# Darlington.net
KiCad netlist of a schematic drawn in Altium Designer
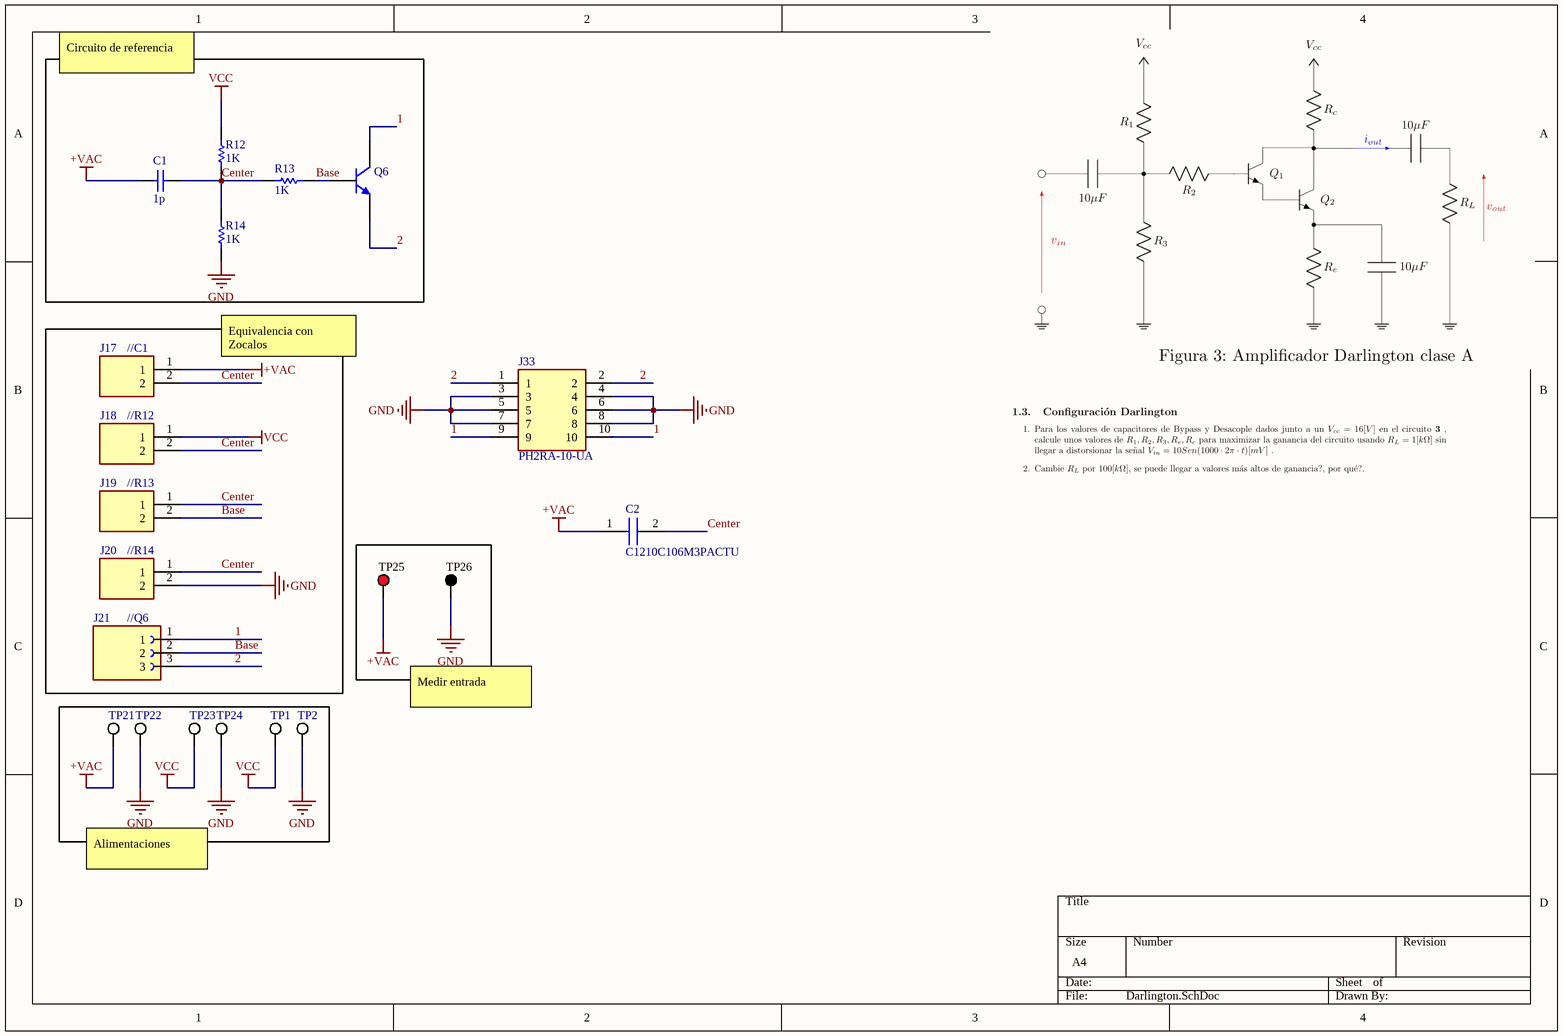
[diagram p0: Darlington.SchDoc]

(export (version "E")
  (design (tool "Eeschema 10.0.6"))
  (components
    (comp (ref "C1")
      (value "1p")
      (description "Capacitor")
      (libsource (lib "Simulation Generic Components") (part "Capacitor"))
    )
    (comp (ref "C2")
      (value "C1210C106M3PACTU")
      (footprint "Cap10uF:C1210")
      (description "Capacitor")
      (fields (field (name "MOUSER PART NUMBER") "80-C1210C106M3P"))
      (libsource (lib "Cap10uF") (part "C1210C106M3PACTU"))
    )
    (comp (ref "J17")
      (value "D01-9970242")
      (footprint "D019970242")
      (description "IC Socket: 2 Pos Receptacle SIL Straight THT Strip")
      (fields (field (name "MOUSER PART NUMBER") "855-D01-9970242"))
      (libsource (lib "Zocalo_2pines") (part "D01-9970242"))
    )
    (comp (ref "J18")
      (value "D01-9970242")
      (footprint "D019970242")
      (description "IC Socket: 2 Pos Receptacle SIL Straight THT Strip")
      (fields (field (name "MOUSER PART NUMBER") "855-D01-9970242"))
      (libsource (lib "Zocalo_2pines") (part "D01-9970242"))
    )
    (comp (ref "J19")
      (value "D01-9970242")
      (footprint "D019970242")
      (description "IC Socket: 2 Pos Receptacle SIL Straight THT Strip")
      (fields (field (name "MOUSER PART NUMBER") "855-D01-9970242"))
      (libsource (lib "Zocalo_2pines") (part "D01-9970242"))
    )
    (comp (ref "J20")
      (value "D01-9970242")
      (footprint "D019970242")
      (description "IC Socket: 2 Pos Receptacle SIL Straight THT Strip")
      (fields (field (name "MOUSER PART NUMBER") "855-D01-9970242"))
      (libsource (lib "Zocalo_2pines") (part "D01-9970242"))
    )
    (comp (ref "J21")
      (value "D01-9970342")
      (footprint "HARWIN_D01-9970342")
      (libsource (lib "Zocalo_3pines") (part "D01-9970342"))
    )
    (comp (ref "J33")
      (value "PH2RA-10-UA")
      (footprint "HDRRA10W64P254_2X5_1270X250X538P")
      (description "CONN HEADER R/A 10POS 2.54MM")
      (fields (field (name "MOUSER PART NUMBER") "737-PH2RA-10-UA"))
      (libsource (lib "PH2RA-10-UA") (part "PH2RA-10-UA"))
    )
    (comp (ref "Q6")
      (value "Bipolar NPN 3 Pins Transistor VBIC Model")
      (libsource (lib "Simulation Generic Components") (part "BJT NPN VBIC"))
    )
    (comp (ref "R12")
      (value "1K")
      (description "Resistor")
      (libsource (lib "Simulation Generic Components") (part "Resistor"))
    )
    (comp (ref "R13")
      (value "1K")
      (description "Resistor")
      (libsource (lib "Simulation Generic Components") (part "Resistor"))
    )
    (comp (ref "R14")
      (value "1K")
      (description "Resistor")
      (libsource (lib "Simulation Generic Components") (part "Resistor"))
    )
    (comp (ref "TP1")
      (value "575-4")
      (footprint "KSTN-575-4")
      (description "Banana Jack, Non-Insulated, 1-Pin THD, RoHS, Bulk")
      (fields (field (name "MANUFACTURER") "Keystone-Electronics"))
      (libsource (lib "Altium Content Vault") (part "TESTPOINT_WHITE"))
    )
    (comp (ref "TP2")
      (value "575-4")
      (footprint "KSTN-575-4")
      (description "Banana Jack, Non-Insulated, 1-Pin THD, RoHS, Bulk")
      (fields (field (name "MANUFACTURER") "Keystone-Electronics"))
      (libsource (lib "Altium Content Vault") (part "TESTPOINT_WHITE"))
    )
    (comp (ref "TP21")
      (value "575-4")
      (footprint "KSTN-575-4")
      (description "Banana Jack, Non-Insulated, 1-Pin THD, RoHS, Bulk")
      (fields (field (name "MANUFACTURER") "Keystone-Electronics"))
      (libsource (lib "Altium Content Vault") (part "TESTPOINT_WHITE"))
    )
    (comp (ref "TP22")
      (value "575-4")
      (footprint "KSTN-575-4")
      (description "Banana Jack, Non-Insulated, 1-Pin THD, RoHS, Bulk")
      (fields (field (name "MANUFACTURER") "Keystone-Electronics"))
      (libsource (lib "Altium Content Vault") (part "TESTPOINT_WHITE"))
    )
    (comp (ref "TP23")
      (value "575-4")
      (footprint "KSTN-575-4")
      (description "Banana Jack, Non-Insulated, 1-Pin THD, RoHS, Bulk")
      (fields (field (name "MANUFACTURER") "Keystone-Electronics"))
      (libsource (lib "Altium Content Vault") (part "TESTPOINT_WHITE"))
    )
    (comp (ref "TP24")
      (value "575-4")
      (footprint "KSTN-575-4")
      (description "Banana Jack, Non-Insulated, 1-Pin THD, RoHS, Bulk")
      (fields (field (name "MANUFACTURER") "Keystone-Electronics"))
      (libsource (lib "Altium Content Vault") (part "TESTPOINT_WHITE"))
    )
    (comp (ref "TP25")
      (value "5010")
      (footprint "KSTN-5010_V")
      (description "Test Point, Red, Through Hole, RoHS, Bulk")
      (fields (field (name "MANUFACTURER") "Keystone"))
      (libsource (lib "Altium Content Vault") (part "TESTPOINT_RED"))
    )
    (comp (ref "TP26")
      (value "5011")
      (footprint "KSTN-5011_V")
      (description "Test Point, Black, Through Hole, RoHS, Bulk")
      (fields (field (name "MANUFACTURER") "Keystone"))
      (libsource (lib "Altium Content Vault") (part "TESTPOINT_BLACK"))
    )
  )
  (nets
    (net (code "1") (name "+VAC") (class "Default")
      (node (ref "C1") (pin "1") (pinfunction "1_1") (pintype "passive"))
      (node (ref "C2") (pin "1") (pinfunction "1_1") (pintype "passive"))
      (node (ref "J17") (pin "1") (pinfunction "1_1") (pintype "passive"))
      (node (ref "TP21") (pin "1") (pinfunction "1_1") (pintype "passive"))
      (node (ref "TP25") (pin "1") (pinfunction "1_1") (pintype "passive"))
    )
    (net (code "2") (name "/1") (class "Default")
      (node (ref "J21") (pin "1") (pinfunction "1_1") (pintype "passive"))
      (node (ref "J33") (pin "10") (pinfunction "10_10") (pintype "passive"))
      (node (ref "J33") (pin "9") (pinfunction "9_9") (pintype "passive"))
      (node (ref "Q6") (pin "1") (pinfunction "C_1") (pintype "passive"))
    )
    (net (code "3") (name "/2") (class "Default")
      (node (ref "J21") (pin "3") (pinfunction "3_3") (pintype "passive"))
      (node (ref "J33") (pin "1") (pinfunction "1_1") (pintype "passive"))
      (node (ref "J33") (pin "2") (pinfunction "2_2") (pintype "passive"))
      (node (ref "Q6") (pin "3") (pinfunction "E_3") (pintype "passive"))
    )
    (net (code "4") (name "/Base") (class "Default")
      (node (ref "J19") (pin "2") (pinfunction "2_2") (pintype "passive"))
      (node (ref "J21") (pin "2") (pinfunction "2_2") (pintype "passive"))
      (node (ref "Q6") (pin "2") (pinfunction "B_2") (pintype "passive"))
      (node (ref "R13") (pin "2") (pinfunction "2_2") (pintype "passive"))
    )
    (net (code "5") (name "/Center") (class "Default")
      (node (ref "C1") (pin "2") (pinfunction "2_2") (pintype "passive"))
      (node (ref "C2") (pin "2") (pinfunction "2_2") (pintype "passive"))
      (node (ref "J17") (pin "2") (pinfunction "2_2") (pintype "passive"))
      (node (ref "J18") (pin "2") (pinfunction "2_2") (pintype "passive"))
      (node (ref "J19") (pin "1") (pinfunction "1_1") (pintype "passive"))
      (node (ref "J20") (pin "1") (pinfunction "1_1") (pintype "passive"))
      (node (ref "R12") (pin "2") (pinfunction "2_2") (pintype "passive"))
      (node (ref "R13") (pin "1") (pinfunction "1_1") (pintype "passive"))
      (node (ref "R14") (pin "2") (pinfunction "2_2") (pintype "passive"))
    )
    (net (code "6") (name "GND") (class "Default")
      (node (ref "J20") (pin "2") (pinfunction "2_2") (pintype "passive"))
      (node (ref "J33") (pin "3") (pinfunction "3_3") (pintype "passive"))
      (node (ref "J33") (pin "4") (pinfunction "4_4") (pintype "passive"))
      (node (ref "J33") (pin "5") (pinfunction "5_5") (pintype "passive"))
      (node (ref "J33") (pin "6") (pinfunction "6_6") (pintype "passive"))
      (node (ref "J33") (pin "7") (pinfunction "7_7") (pintype "passive"))
      (node (ref "J33") (pin "8") (pinfunction "8_8") (pintype "passive"))
      (node (ref "R14") (pin "1") (pinfunction "1_1") (pintype "passive"))
      (node (ref "TP2") (pin "1") (pinfunction "1_1") (pintype "passive"))
      (node (ref "TP22") (pin "1") (pinfunction "1_1") (pintype "passive"))
      (node (ref "TP24") (pin "1") (pinfunction "1_1") (pintype "passive"))
      (node (ref "TP26") (pin "1") (pinfunction "1_1") (pintype "passive"))
    )
    (net (code "7") (name "VCC") (class "Default")
      (node (ref "J18") (pin "1") (pinfunction "1_1") (pintype "passive"))
      (node (ref "R12") (pin "1") (pinfunction "1_1") (pintype "passive"))
      (node (ref "TP1") (pin "1") (pinfunction "1_1") (pintype "passive"))
      (node (ref "TP23") (pin "1") (pinfunction "1_1") (pintype "passive"))
    )
  )
)
